# AI.net
KiCad netlist of a schematic drawn in Altium Designer
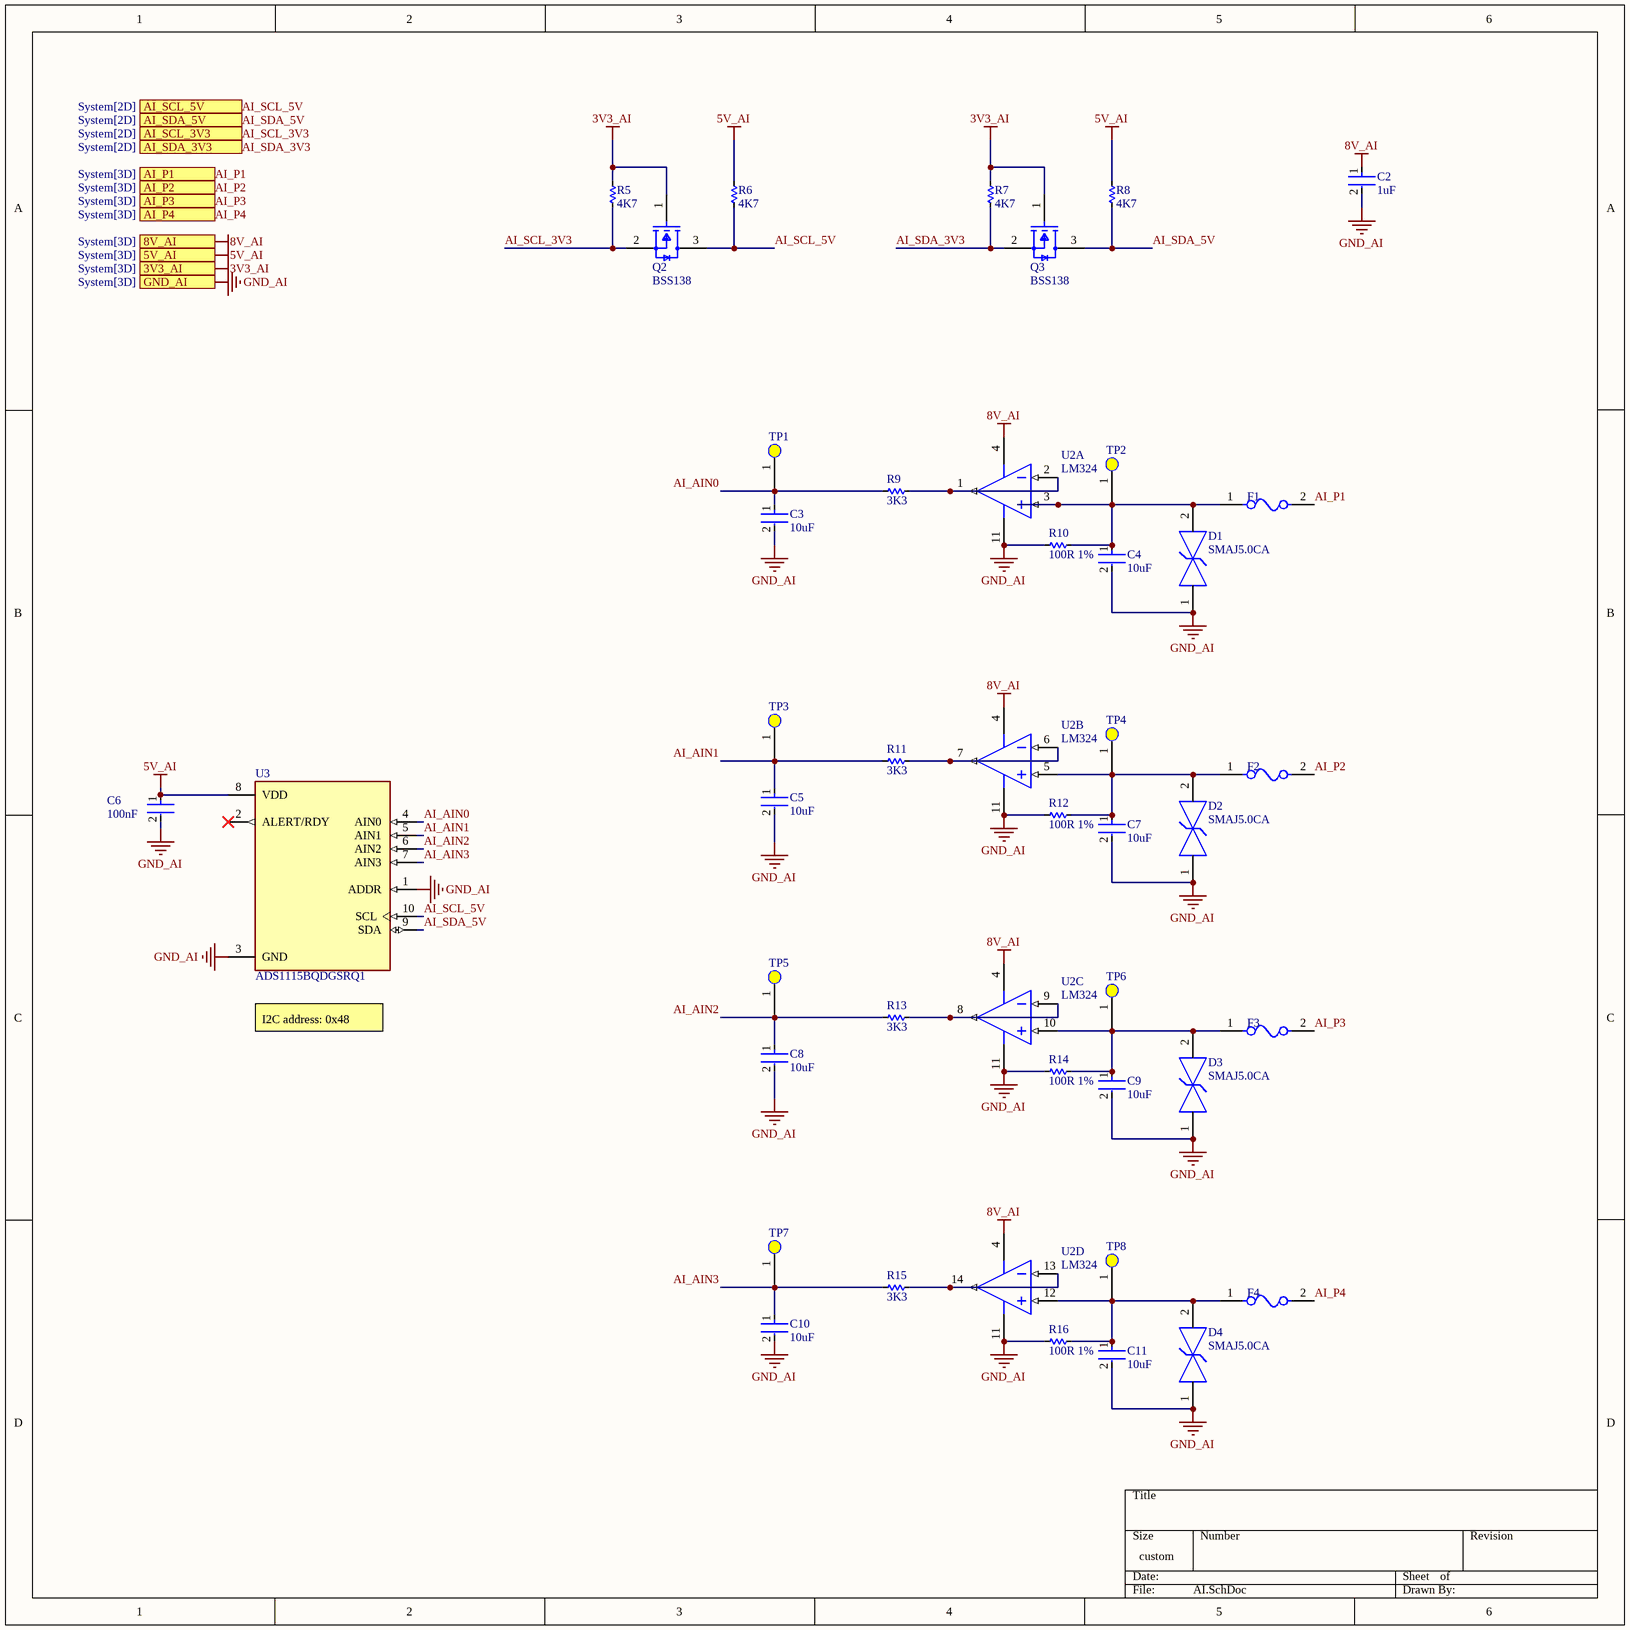
[diagram p0: AI.SchDoc]

(export (version "E")
  (design (tool "Eeschema 10.0.6"))
  (components
    (comp (ref "C2")
      (value "1uF")
      (footprint "FP-GRM18-0_15-MFG")
      (description "CAP CER 1UF 10V X5R 0603")
      (fields
        (field (name "OCTOPART") "https://octopart.com/grm188r61a106ke69d-murata-22851381")
        (field (name "MANUFACTURER PART NUMBER") "GRM188R61A106KE69D")
      )
      (libsource (lib "Altium Content Vault") (part "11868f565c42a9108669ba33697ecf6"))
    )
    (comp (ref "C3")
      (value "10uF")
      (footprint "FP-GRM18-0_15-MFG")
      (description "CAP CER 10UF 10V X5R 0603")
      (fields
        (field (name "OCTOPART") "https://octopart.com/grm188r61a106ke69d-murata-22851381")
        (field (name "MANUFACTURER PART NUMBER") "GRM188R61A106KE69D")
      )
      (libsource (lib "Altium Content Vault") (part "11868f565c42a9108669ba33697ecf6"))
    )
    (comp (ref "C4")
      (value "10uF")
      (footprint "FP-GRM18-0_15-MFG")
      (description "CAP CER 10UF 10V X5R 0603")
      (fields
        (field (name "OCTOPART") "https://octopart.com/grm188r61a106ke69d-murata-22851381")
        (field (name "MANUFACTURER PART NUMBER") "GRM188R61A106KE69D")
      )
      (libsource (lib "Altium Content Vault") (part "11868f565c42a9108669ba33697ecf6"))
    )
    (comp (ref "C5")
      (value "10uF")
      (footprint "FP-GRM18-0_15-MFG")
      (description "CAP CER 10UF 10V X5R 0603")
      (fields
        (field (name "OCTOPART") "https://octopart.com/grm188r61a106ke69d-murata-22851381")
        (field (name "MANUFACTURER PART NUMBER") "GRM188R61A106KE69D")
      )
      (libsource (lib "Altium Content Vault") (part "11868f565c42a9108669ba33697ecf6"))
    )
    (comp (ref "C6")
      (value "100nF")
      (footprint "FP-GRM18-0_15-MFG")
      (description "CAP CER 10V X5R 0603")
      (fields
        (field (name "OCTOPART") "https://octopart.com/grm188r61a106ke69d-murata-22851381")
        (field (name "MANUFACTURER PART NUMBER") "GRM188R61A106KE69D")
      )
      (libsource (lib "Altium Content Vault") (part "11868f565c42a9108669ba33697ecf6"))
    )
    (comp (ref "C7")
      (value "10uF")
      (footprint "FP-GRM18-0_15-MFG")
      (description "CAP CER 10UF 10V X5R 0603")
      (fields
        (field (name "OCTOPART") "https://octopart.com/grm188r61a106ke69d-murata-22851381")
        (field (name "MANUFACTURER PART NUMBER") "GRM188R61A106KE69D")
      )
      (libsource (lib "Altium Content Vault") (part "11868f565c42a9108669ba33697ecf6"))
    )
    (comp (ref "C8")
      (value "10uF")
      (footprint "FP-GRM18-0_15-MFG")
      (description "CAP CER 10UF 10V X5R 0603")
      (fields
        (field (name "OCTOPART") "https://octopart.com/grm188r61a106ke69d-murata-22851381")
        (field (name "MANUFACTURER PART NUMBER") "GRM188R61A106KE69D")
      )
      (libsource (lib "Altium Content Vault") (part "11868f565c42a9108669ba33697ecf6"))
    )
    (comp (ref "C9")
      (value "10uF")
      (footprint "FP-GRM18-0_15-MFG")
      (description "CAP CER 10UF 10V X5R 0603")
      (fields
        (field (name "OCTOPART") "https://octopart.com/grm188r61a106ke69d-murata-22851381")
        (field (name "MANUFACTURER PART NUMBER") "GRM188R61A106KE69D")
      )
      (libsource (lib "Altium Content Vault") (part "11868f565c42a9108669ba33697ecf6"))
    )
    (comp (ref "C10")
      (value "10uF")
      (footprint "FP-GRM18-0_15-MFG")
      (description "CAP CER 10UF 10V X5R 0603")
      (fields
        (field (name "OCTOPART") "https://octopart.com/grm188r61a106ke69d-murata-22851381")
        (field (name "MANUFACTURER PART NUMBER") "GRM188R61A106KE69D")
      )
      (libsource (lib "Altium Content Vault") (part "11868f565c42a9108669ba33697ecf6"))
    )
    (comp (ref "C11")
      (value "10uF")
      (footprint "FP-GRM18-0_15-MFG")
      (description "CAP CER 10UF 10V X5R 0603")
      (fields
        (field (name "OCTOPART") "https://octopart.com/grm188r61a106ke69d-murata-22851381")
        (field (name "MANUFACTURER PART NUMBER") "GRM188R61A106KE69D")
      )
      (libsource (lib "Altium Content Vault") (part "11868f565c42a9108669ba33697ecf6"))
    )
    (comp (ref "D1")
      (value "SMAJ5.0CA")
      (footprint "FP-SMAJ-MFG")
      (description "SMAJ5.0CA TVS Diode 5V 400W SMA(DO-214AC)")
      (fields
        (field (name "OCTOPART") "https://octopart.com/smaj58ca-littelfuse-350202")
        (field (name "MANUFACTURER") "Littelfuse Inc")
      )
      (libsource (lib "Altium Content Vault") (part "89c663e49c8877d2c9d183c2997548d"))
    )
    (comp (ref "D2")
      (value "SMAJ5.0CA")
      (footprint "FP-SMAJ-MFG")
      (description "SMAJ5.0CA TVS Diode 5V 400W SMA(DO-214AC)")
      (fields
        (field (name "OCTOPART") "https://octopart.com/smaj58ca-littelfuse-350202")
        (field (name "MANUFACTURER") "Littelfuse Inc")
      )
      (libsource (lib "Altium Content Vault") (part "89c663e49c8877d2c9d183c2997548d"))
    )
    (comp (ref "D3")
      (value "SMAJ5.0CA")
      (footprint "FP-SMAJ-MFG")
      (description "SMAJ5.0CA TVS Diode 5V 400W SMA(DO-214AC)")
      (fields
        (field (name "OCTOPART") "https://octopart.com/smaj58ca-littelfuse-350202")
        (field (name "MANUFACTURER") "Littelfuse Inc")
      )
      (libsource (lib "Altium Content Vault") (part "89c663e49c8877d2c9d183c2997548d"))
    )
    (comp (ref "D4")
      (value "SMAJ5.0CA")
      (footprint "FP-SMAJ-MFG")
      (description "SMAJ5.0CA TVS Diode 5V 400W SMA(DO-214AC)")
      (fields
        (field (name "OCTOPART") "https://octopart.com/smaj58ca-littelfuse-350202")
        (field (name "MANUFACTURER") "Littelfuse Inc")
      )
      (libsource (lib "Altium Content Vault") (part "89c663e49c8877d2c9d183c2997548d"))
    )
    (comp (ref "F1")
      (value "CLA1683")
      (footprint "FP-0468-MFG")
      (description "1206 0.05A 60V JZ PTC SMD")
      (fields
        (field (name "MANUFACTURER PART NUMBER") "0468.500NR")
        (field (name "OCTOPART") "https://octopart.com/0468.500nr-littelfuse-672821")
      )
      (libsource (lib "Altium Content Vault") (part "5bcf9b9f640e542cf0359d10258e979"))
    )
    (comp (ref "F2")
      (value "CLA1683")
      (footprint "FP-0468-MFG")
      (description "1206 0.05A 60V JZ PTC SMD")
      (fields
        (field (name "MANUFACTURER PART NUMBER") "0468.500NR")
        (field (name "OCTOPART") "https://octopart.com/0468.500nr-littelfuse-672821")
      )
      (libsource (lib "Altium Content Vault") (part "5bcf9b9f640e542cf0359d10258e979"))
    )
    (comp (ref "F3")
      (value "CLA1683")
      (footprint "FP-0468-MFG")
      (description "1206 0.05A 60V JZ PTC SMD")
      (fields
        (field (name "MANUFACTURER PART NUMBER") "0468.500NR")
        (field (name "OCTOPART") "https://octopart.com/0468.500nr-littelfuse-672821")
      )
      (libsource (lib "Altium Content Vault") (part "5bcf9b9f640e542cf0359d10258e979"))
    )
    (comp (ref "F4")
      (value "CLA1683")
      (footprint "FP-0468-MFG")
      (description "1206 0.05A 60V JZ PTC SMD")
      (fields
        (field (name "MANUFACTURER PART NUMBER") "0468.500NR")
        (field (name "OCTOPART") "https://octopart.com/0468.500nr-littelfuse-672821")
      )
      (libsource (lib "Altium Content Vault") (part "5bcf9b9f640e542cf0359d10258e979"))
    )
    (comp (ref "Q2")
      (value "BSS138")
      (footprint "FP-318-08-IPC_B")
      (description "MOSFET N-CH 50V 220MA SOT-23")
      (libsource (lib "Altium Content Vault") (part "3b9c635fedb024a5347a57b145af9cc"))
    )
    (comp (ref "Q3")
      (value "BSS138")
      (footprint "FP-318-08-IPC_B")
      (description "MOSFET N-CH 50V 220MA SOT-23")
      (libsource (lib "Altium Content Vault") (part "3b9c635fedb024a5347a57b145af9cc"))
    )
    (comp (ref "R5")
      (value "4K7")
      (footprint "RES-SMD-0603")
      (description "Res 0603 5%")
      (fields
        (field (name "MANUFACTURER") "Generic Components")
        (field (name "PUBLISHER") "Altium Hobart Technology Centre")
      )
      (libsource (lib "TechMT.VN_Lib_Project v2") (part "Res-SMD"))
    )
    (comp (ref "R6")
      (value "4K7")
      (footprint "RES-SMD-0603")
      (description "Res 0603 5%")
      (fields
        (field (name "MANUFACTURER") "Generic Components")
        (field (name "PUBLISHER") "Altium Hobart Technology Centre")
      )
      (libsource (lib "TechMT.VN_Lib_Project v2") (part "Res-SMD"))
    )
    (comp (ref "R7")
      (value "4K7")
      (footprint "RES-SMD-0603")
      (description "Res 0603 5%")
      (fields
        (field (name "MANUFACTURER") "Generic Components")
        (field (name "PUBLISHER") "Altium Hobart Technology Centre")
      )
      (libsource (lib "TechMT.VN_Lib_Project v2") (part "Res-SMD"))
    )
    (comp (ref "R8")
      (value "4K7")
      (footprint "RES-SMD-0603")
      (description "Res 0603 5%")
      (fields
        (field (name "MANUFACTURER") "Generic Components")
        (field (name "PUBLISHER") "Altium Hobart Technology Centre")
      )
      (libsource (lib "TechMT.VN_Lib_Project v2") (part "Res-SMD"))
    )
    (comp (ref "R9")
      (value "3K3")
      (footprint "RES-SMD-0603")
      (description "Res 0603 5%")
      (fields
        (field (name "MANUFACTURER") "Generic Components")
        (field (name "PUBLISHER") "Altium Hobart Technology Centre")
      )
      (libsource (lib "TechMT.VN_Lib_Project v2") (part "Res-SMD"))
    )
    (comp (ref "R10")
      (value "100R 1%")
      (footprint "RES-SMD-0805")
      (description "Res 0805 1%")
      (fields
        (field (name "MANUFACTURER") "Generic Components")
        (field (name "PUBLISHER") "Altium Hobart Technology Centre")
      )
      (libsource (lib "TechMT.VN_Lib_Project v2") (part "Res-SMD"))
    )
    (comp (ref "R11")
      (value "3K3")
      (footprint "RES-SMD-0603")
      (description "Res 0603 5%")
      (fields
        (field (name "MANUFACTURER") "Generic Components")
        (field (name "PUBLISHER") "Altium Hobart Technology Centre")
      )
      (libsource (lib "TechMT.VN_Lib_Project v2") (part "Res-SMD"))
    )
    (comp (ref "R12")
      (value "100R 1%")
      (footprint "RES-SMD-0805")
      (description "Res 0805 1%")
      (fields
        (field (name "MANUFACTURER") "Generic Components")
        (field (name "PUBLISHER") "Altium Hobart Technology Centre")
      )
      (libsource (lib "TechMT.VN_Lib_Project v2") (part "Res-SMD"))
    )
    (comp (ref "R13")
      (value "3K3")
      (footprint "RES-SMD-0603")
      (description "Res 0603 5%")
      (fields
        (field (name "MANUFACTURER") "Generic Components")
        (field (name "PUBLISHER") "Altium Hobart Technology Centre")
      )
      (libsource (lib "TechMT.VN_Lib_Project v2") (part "Res-SMD"))
    )
    (comp (ref "R14")
      (value "100R 1%")
      (footprint "RES-SMD-0805")
      (description "Res 0805 1%")
      (fields
        (field (name "MANUFACTURER") "Generic Components")
        (field (name "PUBLISHER") "Altium Hobart Technology Centre")
      )
      (libsource (lib "TechMT.VN_Lib_Project v2") (part "Res-SMD"))
    )
    (comp (ref "R15")
      (value "3K3")
      (footprint "RES-SMD-0603")
      (description "Res 0603 5%")
      (fields
        (field (name "MANUFACTURER") "Generic Components")
        (field (name "PUBLISHER") "Altium Hobart Technology Centre")
      )
      (libsource (lib "TechMT.VN_Lib_Project v2") (part "Res-SMD"))
    )
    (comp (ref "R16")
      (value "100R 1%")
      (footprint "RES-SMD-0805")
      (description "Res 0805 1%")
      (fields
        (field (name "MANUFACTURER") "Generic Components")
        (field (name "PUBLISHER") "Altium Hobart Technology Centre")
      )
      (libsource (lib "TechMT.VN_Lib_Project v2") (part "Res-SMD"))
    )
    (comp (ref "TP1")
      (value "Test Point")
      (footprint "Test Point")
      (libsource (lib "atlab_altium_lib") (part "Test Point"))
    )
    (comp (ref "TP2")
      (value "Test Point")
      (footprint "Test Point")
      (libsource (lib "atlab_altium_lib") (part "Test Point"))
    )
    (comp (ref "TP3")
      (value "Test Point")
      (footprint "Test Point")
      (libsource (lib "atlab_altium_lib") (part "Test Point"))
    )
    (comp (ref "TP4")
      (value "Test Point")
      (footprint "Test Point")
      (libsource (lib "atlab_altium_lib") (part "Test Point"))
    )
    (comp (ref "TP5")
      (value "Test Point")
      (footprint "Test Point")
      (libsource (lib "atlab_altium_lib") (part "Test Point"))
    )
    (comp (ref "TP6")
      (value "Test Point")
      (footprint "Test Point")
      (libsource (lib "atlab_altium_lib") (part "Test Point"))
    )
    (comp (ref "TP7")
      (value "Test Point")
      (footprint "Test Point")
      (libsource (lib "atlab_altium_lib") (part "Test Point"))
    )
    (comp (ref "TP8")
      (value "Test Point")
      (footprint "Test Point")
      (libsource (lib "atlab_altium_lib") (part "Test Point"))
    )
    (comp (ref "U2")
      (value "LM324")
      (footprint "D0014A_N")
      (fields (field (name "PARTNUMBER") "TL084CDR") (field (name "MANUFACTURER") "Texas Instruments"))
      (libsource (lib "Altium Content Vault") (part "TI-TLXX4X_MC3403-X14"))
    )
    (comp (ref "U3")
      (value "ADS1115BQDGSRQ1")
      (footprint "SOP50P490X110-10N")
      (description "Automotive 16-bit, 860-SPS, 4-ch, delta-sigma ADC with PGA, oscillator, VREF, comparator and I2C")
      (fields (field (name "MF") "Texas Instruments"))
      (libsource (lib "Lib_NHN") (part "ADS1115BQDGSRQ1"))
    )
  )
  (nets
    (net (code "1") (name "/AI_AIN0") (class "Default")
      (node (ref "C3") (pin "1") (pinfunction "1_1") (pintype "passive"))
      (node (ref "R9") (pin "2") (pinfunction "2_2") (pintype "passive"))
      (node (ref "TP1") (pin "1") (pinfunction "Test_Point_1") (pintype "passive"))
      (node (ref "U3") (pin "4") (pinfunction "AIN0_4") (pintype "input"))
    )
    (net (code "2") (name "/AI_AIN1") (class "Default")
      (node (ref "C5") (pin "1") (pinfunction "1_1") (pintype "passive"))
      (node (ref "R11") (pin "2") (pinfunction "2_2") (pintype "passive"))
      (node (ref "TP3") (pin "1") (pinfunction "Test_Point_1") (pintype "passive"))
      (node (ref "U3") (pin "5") (pinfunction "AIN1_5") (pintype "input"))
    )
    (net (code "3") (name "/AI_AIN2") (class "Default")
      (node (ref "C8") (pin "1") (pinfunction "1_1") (pintype "passive"))
      (node (ref "R13") (pin "2") (pinfunction "2_2") (pintype "passive"))
      (node (ref "TP5") (pin "1") (pinfunction "Test_Point_1") (pintype "passive"))
      (node (ref "U3") (pin "6") (pinfunction "AIN2_6") (pintype "input"))
    )
    (net (code "4") (name "/AI_AIN3") (class "Default")
      (node (ref "C10") (pin "1") (pinfunction "1_1") (pintype "passive"))
      (node (ref "R15") (pin "2") (pinfunction "2_2") (pintype "passive"))
      (node (ref "TP7") (pin "1") (pinfunction "Test_Point_1") (pintype "passive"))
      (node (ref "U3") (pin "7") (pinfunction "AIN3_7") (pintype "input"))
    )
    (net (code "5") (name "/AI_P1") (class "Default")
      (node (ref "F1") (pin "2") (pinfunction "2_2") (pintype "passive"))
    )
    (net (code "6") (name "/AI_P2") (class "Default")
      (node (ref "F2") (pin "2") (pinfunction "2_2") (pintype "passive"))
    )
    (net (code "7") (name "/AI_P3") (class "Default")
      (node (ref "F3") (pin "2") (pinfunction "2_2") (pintype "passive"))
    )
    (net (code "8") (name "/AI_P4") (class "Default")
      (node (ref "F4") (pin "2") (pinfunction "2_2") (pintype "passive"))
    )
    (net (code "9") (name "/AI_SCL_3V3") (class "Default")
      (node (ref "Q2") (pin "2") (pinfunction "S_2") (pintype "passive"))
      (node (ref "R5") (pin "2") (pinfunction "2_2") (pintype "passive"))
    )
    (net (code "10") (name "/AI_SCL_5V") (class "Default")
      (node (ref "Q2") (pin "3") (pinfunction "D_3") (pintype "passive"))
      (node (ref "R6") (pin "2") (pinfunction "2_2") (pintype "passive"))
      (node (ref "U3") (pin "10") (pinfunction "SCL_10") (pintype "input"))
    )
    (net (code "11") (name "/AI_SDA_3V3") (class "Default")
      (node (ref "Q3") (pin "2") (pinfunction "S_2") (pintype "passive"))
      (node (ref "R7") (pin "2") (pinfunction "2_2") (pintype "passive"))
    )
    (net (code "12") (name "/AI_SDA_5V") (class "Default")
      (node (ref "Q3") (pin "3") (pinfunction "D_3") (pintype "passive"))
      (node (ref "R8") (pin "2") (pinfunction "2_2") (pintype "passive"))
      (node (ref "U3") (pin "9") (pinfunction "SDA_9") (pintype "bidirectional"))
    )
    (net (code "13") (name "3V3_AI") (class "Default")
      (node (ref "Q2") (pin "1") (pinfunction "G_1") (pintype "passive"))
      (node (ref "Q3") (pin "1") (pinfunction "G_1") (pintype "passive"))
      (node (ref "R5") (pin "1") (pinfunction "1_1") (pintype "passive"))
      (node (ref "R7") (pin "1") (pinfunction "1_1") (pintype "passive"))
    )
    (net (code "14") (name "5V_AI") (class "Default")
      (node (ref "C6") (pin "1") (pinfunction "1_1") (pintype "passive"))
      (node (ref "R6") (pin "1") (pinfunction "1_1") (pintype "passive"))
      (node (ref "R8") (pin "1") (pinfunction "1_1") (pintype "passive"))
      (node (ref "U3") (pin "8") (pinfunction "VDD_8") (pintype "power_in"))
    )
    (net (code "15") (name "8V_AI") (class "Default")
      (node (ref "C2") (pin "1") (pinfunction "1_1") (pintype "passive"))
      (node (ref "U2") (pin "4") (pinfunction "VCC+_4") (pintype "power_in"))
    )
    (net (code "16") (name "GND_AI") (class "Default")
      (node (ref "C10") (pin "2") (pinfunction "2_2") (pintype "passive"))
      (node (ref "C11") (pin "2") (pinfunction "2_2") (pintype "passive"))
      (node (ref "C2") (pin "2") (pinfunction "2_2") (pintype "passive"))
      (node (ref "C3") (pin "2") (pinfunction "2_2") (pintype "passive"))
      (node (ref "C4") (pin "2") (pinfunction "2_2") (pintype "passive"))
      (node (ref "C5") (pin "2") (pinfunction "2_2") (pintype "passive"))
      (node (ref "C6") (pin "2") (pinfunction "2_2") (pintype "passive"))
      (node (ref "C7") (pin "2") (pinfunction "2_2") (pintype "passive"))
      (node (ref "C8") (pin "2") (pinfunction "2_2") (pintype "passive"))
      (node (ref "C9") (pin "2") (pinfunction "2_2") (pintype "passive"))
      (node (ref "D1") (pin "1") (pinfunction "1_1") (pintype "passive"))
      (node (ref "D2") (pin "1") (pinfunction "1_1") (pintype "passive"))
      (node (ref "D3") (pin "1") (pinfunction "1_1") (pintype "passive"))
      (node (ref "D4") (pin "1") (pinfunction "1_1") (pintype "passive"))
      (node (ref "R10") (pin "2") (pinfunction "2_2") (pintype "passive"))
      (node (ref "R12") (pin "2") (pinfunction "2_2") (pintype "passive"))
      (node (ref "R14") (pin "2") (pinfunction "2_2") (pintype "passive"))
      (node (ref "R16") (pin "2") (pinfunction "2_2") (pintype "passive"))
      (node (ref "U2") (pin "11") (pinfunction "VCC-_11") (pintype "power_in"))
      (node (ref "U3") (pin "1") (pinfunction "ADDR_1") (pintype "input"))
      (node (ref "U3") (pin "3") (pinfunction "GND_3") (pintype "power_in"))
    )
    (net (code "17") (name "Net-(TP2-Test_Point)") (class "Default")
      (node (ref "C4") (pin "1") (pinfunction "1_1") (pintype "passive"))
      (node (ref "D1") (pin "2") (pinfunction "2_2") (pintype "passive"))
      (node (ref "F1") (pin "1") (pinfunction "1_1") (pintype "passive"))
      (node (ref "R10") (pin "1") (pinfunction "1_1") (pintype "passive"))
      (node (ref "TP2") (pin "1") (pinfunction "Test_Point_1") (pintype "passive"))
      (node (ref "U2") (pin "3") (pinfunction "IN1+_3") (pintype "input"))
    )
    (net (code "18") (name "Net-(TP4-Test_Point)") (class "Default")
      (node (ref "C7") (pin "1") (pinfunction "1_1") (pintype "passive"))
      (node (ref "D2") (pin "2") (pinfunction "2_2") (pintype "passive"))
      (node (ref "F2") (pin "1") (pinfunction "1_1") (pintype "passive"))
      (node (ref "R12") (pin "1") (pinfunction "1_1") (pintype "passive"))
      (node (ref "TP4") (pin "1") (pinfunction "Test_Point_1") (pintype "passive"))
      (node (ref "U2") (pin "5") (pinfunction "IN2+_5") (pintype "input"))
    )
    (net (code "19") (name "Net-(TP6-Test_Point)") (class "Default")
      (node (ref "C9") (pin "1") (pinfunction "1_1") (pintype "passive"))
      (node (ref "D3") (pin "2") (pinfunction "2_2") (pintype "passive"))
      (node (ref "F3") (pin "1") (pinfunction "1_1") (pintype "passive"))
      (node (ref "R14") (pin "1") (pinfunction "1_1") (pintype "passive"))
      (node (ref "TP6") (pin "1") (pinfunction "Test_Point_1") (pintype "passive"))
      (node (ref "U2") (pin "10") (pinfunction "IN3+_10") (pintype "input"))
    )
    (net (code "20") (name "Net-(TP8-Test_Point)") (class "Default")
      (node (ref "C11") (pin "1") (pinfunction "1_1") (pintype "passive"))
      (node (ref "D4") (pin "2") (pinfunction "2_2") (pintype "passive"))
      (node (ref "F4") (pin "1") (pinfunction "1_1") (pintype "passive"))
      (node (ref "R16") (pin "1") (pinfunction "1_1") (pintype "passive"))
      (node (ref "TP8") (pin "1") (pinfunction "Test_Point_1") (pintype "passive"))
      (node (ref "U2") (pin "12") (pinfunction "IN4+_12") (pintype "input"))
    )
    (net (code "21") (name "Net-(U2A-IN1-)") (class "Default")
      (node (ref "R9") (pin "1") (pinfunction "1_1") (pintype "passive"))
      (node (ref "U2") (pin "1") (pinfunction "OUT1_1") (pintype "output"))
      (node (ref "U2") (pin "2") (pinfunction "IN1-_2") (pintype "input"))
    )
    (net (code "22") (name "Net-(U2B-IN2-)") (class "Default")
      (node (ref "R11") (pin "1") (pinfunction "1_1") (pintype "passive"))
      (node (ref "U2") (pin "6") (pinfunction "IN2-_6") (pintype "input"))
      (node (ref "U2") (pin "7") (pinfunction "OUT2_7") (pintype "output"))
    )
    (net (code "23") (name "Net-(U2C-IN3-)") (class "Default")
      (node (ref "R13") (pin "1") (pinfunction "1_1") (pintype "passive"))
      (node (ref "U2") (pin "8") (pinfunction "OUT3_8") (pintype "output"))
      (node (ref "U2") (pin "9") (pinfunction "IN3-_9") (pintype "input"))
    )
    (net (code "24") (name "Net-(U2D-IN4-)") (class "Default")
      (node (ref "R15") (pin "1") (pinfunction "1_1") (pintype "passive"))
      (node (ref "U2") (pin "13") (pinfunction "IN4-_13") (pintype "input"))
      (node (ref "U2") (pin "14") (pinfunction "OUT4_14") (pintype "output"))
    )
    (net (code "25") (name "unconnected-(U3-ALERT{slash}RDY-Pad2)") (class "Default")
      (node (ref "U3") (pin "2") (pinfunction "ALERT/RDY_2") (pintype "output+no_connect"))
    )
  )
)
